# Cores_POWER.net
KiCad netlist of a schematic drawn in Altium Designer
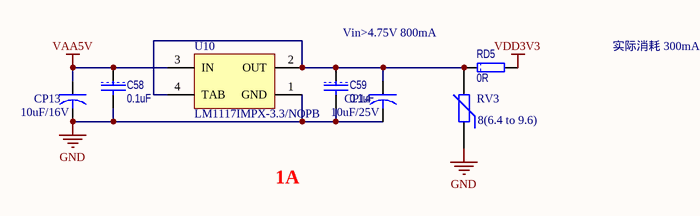
[diagram p0: Cores POWER.SchDoc]

(export (version "E")
  (design (tool "Eeschema 10.0.6"))
  (components
    (comp (ref "C58")
      (value "0.1uF")
      (footprint "1608[0603]")
      (description "Capacitor")
      (fields (field (name "MANUFACTURER") "TDK"))
      (libsource (lib "*") (part "CAP"))
    )
    (comp (ref "C59")
      (value "0.1uF")
      (footprint "1608[0603]")
      (description "Capacitor")
      (fields (field (name "MANUFACTURER") "TDK"))
      (libsource (lib "*") (part "CAP"))
    )
    (comp (ref "CP13")
      (value "10uF/16V")
      (footprint "3216[1206]")
      (description "Tantalum Capacitor")
      (libsource (lib "*") (part "CAPACITOR"))
    )
    (comp (ref "CP14")
      (value "10uF/25V")
      (footprint "6032")
      (description "Tantalum Capacitor")
      (libsource (lib "*") (part "CAPACITOR"))
    )
    (comp (ref "RD5")
      (value "0R")
      (footprint "0603RT")
      (description "RES")
      (fields (field (name "MANUFACTURER") "vishay"))
      (libsource (lib "*") (part "RES"))
    )
    (comp (ref "RV3")
      (value "8(6.4 to 9.6)")
      (footprint "0603RV")
      (description "压敏电阻")
      (fields (field (name "PUBLISHER") "Altium Limited"))
      (libsource (lib "Miscellaneous Devices") (part "Res Varistor"))
    )
    (comp (ref "U10")
      (value "LM1117IMPX-3.3/NOPB")
      (footprint "MP04A_N")
      (description "800mA Low-Dropout Linear Regulator, 4-pin SOT-223, Pb-Free")
      (fields
        (field (name "PARTNUMBER") "LM1117MPX-3.3/NOPB")
        (field (name "MANUFACTURER") "National Semiconductor")
        (field (name "PUBLISHER") "Altium Limited")
      )
      (libsource (lib "NSC LDO") (part "LM1117MPX-3.3/NOPB"))
    )
  )
  (nets
    (net (code "1") (name "GND") (class "Default")
      (node (ref "C58") (pin "2") (pinfunction "2_2") (pintype "passive"))
      (node (ref "C59") (pin "2") (pinfunction "2_2") (pintype "passive"))
      (node (ref "CP13") (pin "2") (pinfunction "2_2") (pintype "passive"))
      (node (ref "CP14") (pin "2") (pinfunction "2_2") (pintype "passive"))
      (node (ref "RV3") (pin "1") (pinfunction "1_1") (pintype "passive"))
      (node (ref "U10") (pin "1") (pinfunction "GND_1") (pintype "power_in"))
    )
    (net (code "2") (name "Net-(U10-OUT)") (class "Default")
      (node (ref "C59") (pin "1") (pinfunction "1_1") (pintype "passive"))
      (node (ref "CP14") (pin "1") (pinfunction "1_1") (pintype "passive"))
      (node (ref "RD5") (pin "1") (pinfunction "1_1") (pintype "passive"))
      (node (ref "RV3") (pin "2") (pinfunction "2_2") (pintype "passive"))
      (node (ref "U10") (pin "2") (pinfunction "OUT_2") (pintype "power_in"))
      (node (ref "U10") (pin "4") (pinfunction "TAB_4") (pintype "power_in"))
    )
    (net (code "3") (name "VAA5V") (class "Default")
      (node (ref "C58") (pin "1") (pinfunction "1_1") (pintype "passive"))
      (node (ref "CP13") (pin "1") (pinfunction "1_1") (pintype "passive"))
      (node (ref "U10") (pin "3") (pinfunction "IN_3") (pintype "power_in"))
    )
    (net (code "4") (name "VDD3V3") (class "Default")
      (node (ref "RD5") (pin "2") (pinfunction "2_2") (pintype "passive"))
    )
  )
)
